# CPLD.net
KiCad netlist of a schematic drawn in Altium Designer
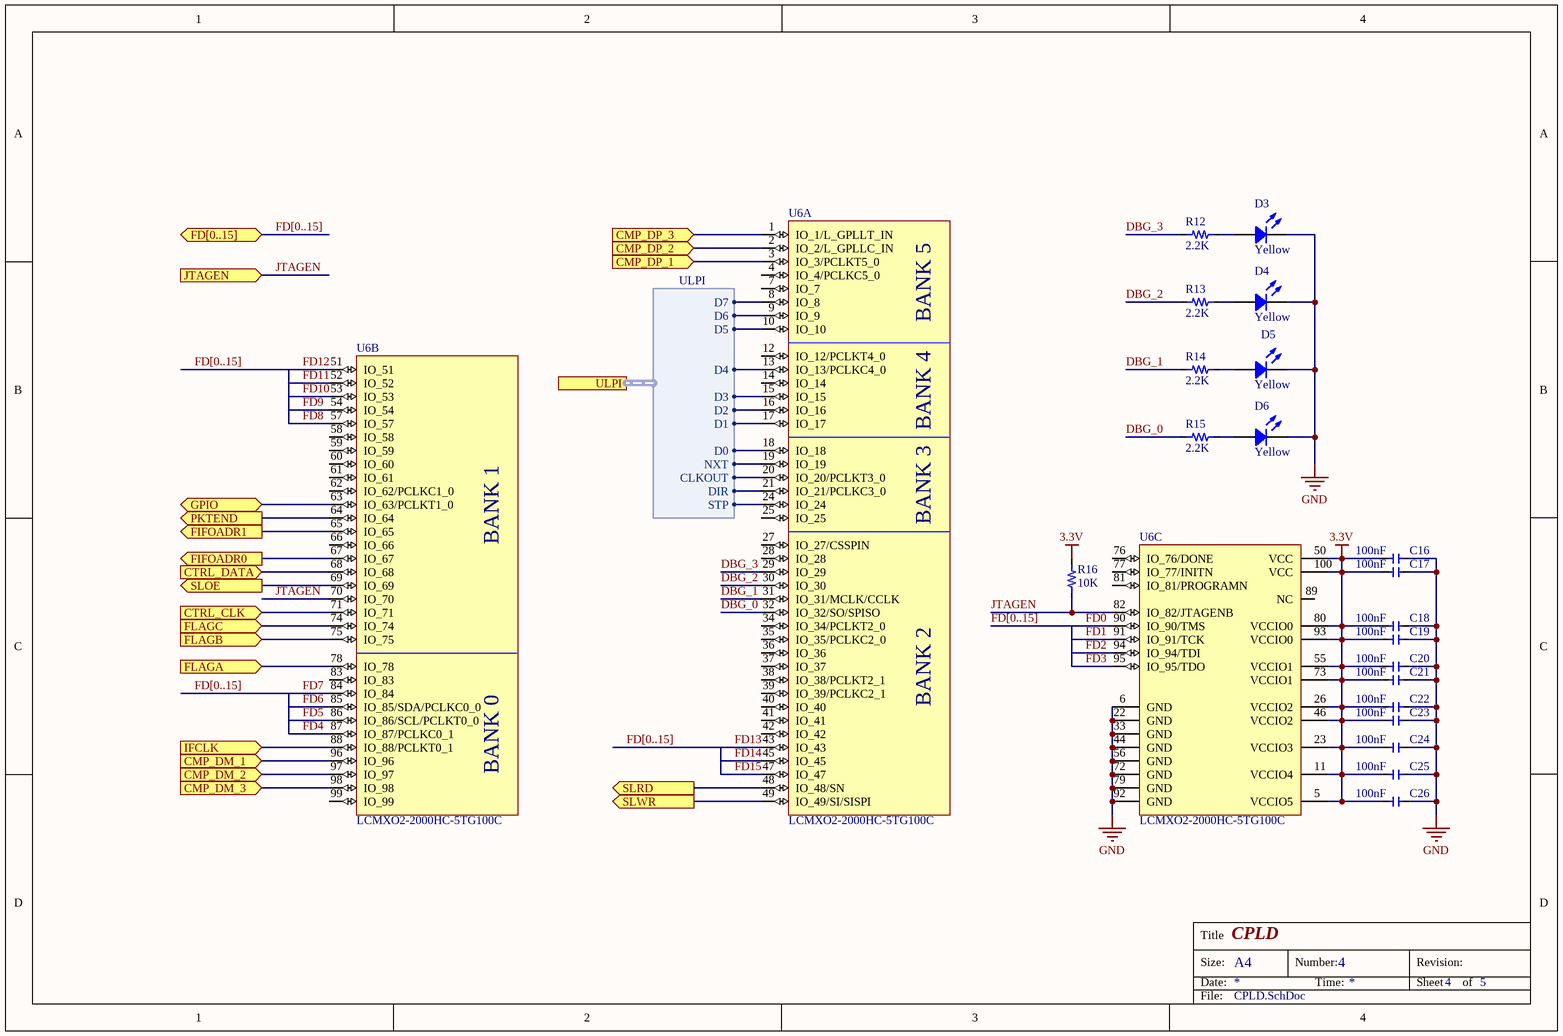
[diagram p0: CPLD.SchDoc]

(export (version "E")
  (design (tool "Eeschema 10.0.6"))
  (components
    (comp (ref "C16")
      (value "100nF")
      (footprint "CAP 0402/1005")
      (description "CAP CER 100NF 25V X5R 0402")
      (fields (field (name "PART NUMBER") "GRM155R61E104KA87D") (field (name "MANUFACTURER") "Murata"))
      (libsource (lib "Mengsklib") (part "Capacitor"))
    )
    (comp (ref "C17")
      (value "100nF")
      (footprint "CAP 0402/1005")
      (description "CAP CER 100NF 25V X5R 0402")
      (fields (field (name "PART NUMBER") "GRM155R61E104KA87D") (field (name "MANUFACTURER") "Murata"))
      (libsource (lib "Mengsklib") (part "Capacitor"))
    )
    (comp (ref "C18")
      (value "100nF")
      (footprint "CAP 0402/1005")
      (description "CAP CER 100NF 25V X5R 0402")
      (fields (field (name "PART NUMBER") "GRM155R61E104KA87D") (field (name "MANUFACTURER") "Murata"))
      (libsource (lib "Mengsklib") (part "Capacitor"))
    )
    (comp (ref "C19")
      (value "100nF")
      (footprint "CAP 0402/1005")
      (description "CAP CER 100NF 25V X5R 0402")
      (fields (field (name "PART NUMBER") "GRM155R61E104KA87D") (field (name "MANUFACTURER") "Murata"))
      (libsource (lib "Mengsklib") (part "Capacitor"))
    )
    (comp (ref "C20")
      (value "100nF")
      (footprint "CAP 0402/1005")
      (description "CAP CER 100NF 25V X5R 0402")
      (fields (field (name "PART NUMBER") "GRM155R61E104KA87D") (field (name "MANUFACTURER") "Murata"))
      (libsource (lib "Mengsklib") (part "Capacitor"))
    )
    (comp (ref "C21")
      (value "100nF")
      (footprint "CAP 0402/1005")
      (description "CAP CER 100NF 25V X5R 0402")
      (fields (field (name "PART NUMBER") "GRM155R61E104KA87D") (field (name "MANUFACTURER") "Murata"))
      (libsource (lib "Mengsklib") (part "Capacitor"))
    )
    (comp (ref "C22")
      (value "100nF")
      (footprint "CAP 0402/1005")
      (description "CAP CER 100NF 25V X5R 0402")
      (fields (field (name "PART NUMBER") "GRM155R61E104KA87D") (field (name "MANUFACTURER") "Murata"))
      (libsource (lib "Mengsklib") (part "Capacitor"))
    )
    (comp (ref "C23")
      (value "100nF")
      (footprint "CAP 0402/1005")
      (description "CAP CER 100NF 25V X5R 0402")
      (fields (field (name "PART NUMBER") "GRM155R61E104KA87D") (field (name "MANUFACTURER") "Murata"))
      (libsource (lib "Mengsklib") (part "Capacitor"))
    )
    (comp (ref "C24")
      (value "100nF")
      (footprint "CAP 0402/1005")
      (description "CAP CER 100NF 25V X5R 0402")
      (fields (field (name "PART NUMBER") "GRM155R61E104KA87D") (field (name "MANUFACTURER") "Murata"))
      (libsource (lib "Mengsklib") (part "Capacitor"))
    )
    (comp (ref "C25")
      (value "100nF")
      (footprint "CAP 0402/1005")
      (description "CAP CER 100NF 25V X5R 0402")
      (fields (field (name "PART NUMBER") "GRM155R61E104KA87D") (field (name "MANUFACTURER") "Murata"))
      (libsource (lib "Mengsklib") (part "Capacitor"))
    )
    (comp (ref "C26")
      (value "100nF")
      (footprint "CAP 0402/1005")
      (description "CAP CER 100NF 25V X5R 0402")
      (fields (field (name "PART NUMBER") "GRM155R61E104KA87D") (field (name "MANUFACTURER") "Murata"))
      (libsource (lib "Mengsklib") (part "Capacitor"))
    )
    (comp (ref "D3")
      (value "Yellow")
      (footprint "LED 0603/1608 YELLOW")
      (description "LED YELLOW CLEAR 0603 SMD")
      (fields
        (field (name "COLOUR") "Yellow")
        (field (name "PART NUMBER") "LTST-C191KSKT")
        (field (name "MANUFACTURER") "Lite-On Inc.")
      )
      (libsource (lib "Mengsklib") (part "LED"))
    )
    (comp (ref "D4")
      (value "Yellow")
      (footprint "LED 0603/1608 YELLOW")
      (description "LED YELLOW CLEAR 0603 SMD")
      (fields
        (field (name "COLOUR") "Yellow")
        (field (name "PART NUMBER") "LTST-C191KSKT")
        (field (name "MANUFACTURER") "Lite-On Inc.")
      )
      (libsource (lib "Mengsklib") (part "LED"))
    )
    (comp (ref "D5")
      (value "Yellow")
      (footprint "LED 0603/1608 YELLOW")
      (description "LED YELLOW CLEAR 0603 SMD")
      (fields
        (field (name "COLOUR") "Yellow")
        (field (name "PART NUMBER") "LTST-C191KSKT")
        (field (name "MANUFACTURER") "Lite-On Inc.")
      )
      (libsource (lib "Mengsklib") (part "LED"))
    )
    (comp (ref "D6")
      (value "Yellow")
      (footprint "LED 0603/1608 YELLOW")
      (description "LED YELLOW CLEAR 0603 SMD")
      (fields
        (field (name "COLOUR") "Yellow")
        (field (name "PART NUMBER") "LTST-C191KSKT")
        (field (name "MANUFACTURER") "Lite-On Inc.")
      )
      (libsource (lib "Mengsklib") (part "LED"))
    )
    (comp (ref "R12")
      (value "2.2K")
      (footprint "RES 0402/1005")
      (description "RES SMD 2.2K OHM 1% 1/16W 0402")
      (fields (field (name "PART NUMBER") "RC0402FR-072K2L") (field (name "MANUFACTURER") "Yageo"))
      (libsource (lib "Mengsklib") (part "Resistor"))
    )
    (comp (ref "R13")
      (value "2.2K")
      (footprint "RES 0402/1005")
      (description "RES SMD 2.2K OHM 1% 1/16W 0402")
      (fields (field (name "PART NUMBER") "RC0402FR-072K2L") (field (name "MANUFACTURER") "Yageo"))
      (libsource (lib "Mengsklib") (part "Resistor"))
    )
    (comp (ref "R14")
      (value "2.2K")
      (footprint "RES 0402/1005")
      (description "RES SMD 2.2K OHM 1% 1/16W 0402")
      (fields (field (name "PART NUMBER") "RC0402FR-072K2L") (field (name "MANUFACTURER") "Yageo"))
      (libsource (lib "Mengsklib") (part "Resistor"))
    )
    (comp (ref "R15")
      (value "2.2K")
      (footprint "RES 0402/1005")
      (description "RES SMD 2.2K OHM 1% 1/16W 0402")
      (fields (field (name "PART NUMBER") "RC0402FR-072K2L") (field (name "MANUFACTURER") "Yageo"))
      (libsource (lib "Mengsklib") (part "Resistor"))
    )
    (comp (ref "R16")
      (value "10K")
      (footprint "RES 0402/1005")
      (description "RES SMD 10K OHM 1% 1/16W 0402")
      (fields (field (name "PART NUMBER") "RC0402FR-0710KL") (field (name "MANUFACTURER") "Yageo"))
      (libsource (lib "Mengsklib") (part "Resistor"))
    )
    (comp (ref "U6")
      (value "LCMXO2-2000HC-5TG100C")
      (footprint "NXP LQFP-100 14x14mm")
      (description "FPGA, MACHXO2, 2112 LUTs")
      (fields (field (name "MANUFACTURER") "Lattice"))
      (libsource (lib "Mengsklib") (part "LCMXO2-2000HC-5TG100"))
    )
  )
  (nets
    (net (code "2") (name "/CLKOUT") (class "Default")
      (node (ref "U6") (pin "20") (pinfunction "IO_20/PCLKT3_0_20") (pintype "bidirectional"))
    )
    (net (code "3") (name "/CMP_DM_1") (class "Default")
      (node (ref "U6") (pin "96") (pinfunction "IO_96_96") (pintype "bidirectional"))
    )
    (net (code "4") (name "/CMP_DM_2") (class "Default")
      (node (ref "U6") (pin "97") (pinfunction "IO_97_97") (pintype "bidirectional"))
    )
    (net (code "5") (name "/CMP_DM_3") (class "Default")
      (node (ref "U6") (pin "98") (pinfunction "IO_98_98") (pintype "bidirectional"))
    )
    (net (code "6") (name "/CMP_DP_1") (class "Default")
      (node (ref "U6") (pin "3") (pinfunction "IO_3/PCLKT5_0_3") (pintype "bidirectional"))
    )
    (net (code "7") (name "/CMP_DP_2") (class "Default")
      (node (ref "U6") (pin "2") (pinfunction "IO_2/L_GPLLC_IN_2") (pintype "bidirectional"))
    )
    (net (code "8") (name "/CMP_DP_3") (class "Default")
      (node (ref "U6") (pin "1") (pinfunction "IO_1/L_GPLLT_IN_1") (pintype "bidirectional"))
    )
    (net (code "9") (name "/CTRL_CLK") (class "Default")
      (node (ref "U6") (pin "71") (pinfunction "IO_71_71") (pintype "bidirectional"))
    )
    (net (code "10") (name "/CTRL_DATA") (class "Default")
      (node (ref "U6") (pin "68") (pinfunction "IO_68_68") (pintype "bidirectional"))
    )
    (net (code "11") (name "/D0") (class "Default")
      (node (ref "U6") (pin "18") (pinfunction "IO_18_18") (pintype "bidirectional"))
    )
    (net (code "12") (name "/D1") (class "Default")
      (node (ref "U6") (pin "17") (pinfunction "IO_17_17") (pintype "bidirectional"))
    )
    (net (code "13") (name "/D2") (class "Default")
      (node (ref "U6") (pin "16") (pinfunction "IO_16_16") (pintype "bidirectional"))
    )
    (net (code "14") (name "/D3") (class "Default")
      (node (ref "U6") (pin "15") (pinfunction "IO_15_15") (pintype "bidirectional"))
    )
    (net (code "15") (name "/D4") (class "Default")
      (node (ref "U6") (pin "13") (pinfunction "IO_13/PCLKC4_0_13") (pintype "bidirectional"))
    )
    (net (code "16") (name "/D5") (class "Default")
      (node (ref "U6") (pin "10") (pinfunction "IO_10_10") (pintype "bidirectional"))
    )
    (net (code "17") (name "/D6") (class "Default")
      (node (ref "U6") (pin "9") (pinfunction "IO_9_9") (pintype "bidirectional"))
    )
    (net (code "18") (name "/D7") (class "Default")
      (node (ref "U6") (pin "8") (pinfunction "IO_8_8") (pintype "bidirectional"))
    )
    (net (code "19") (name "/DBG_0") (class "Default")
      (node (ref "R15") (pin "2") (pinfunction "2_2") (pintype "passive"))
      (node (ref "U6") (pin "32") (pinfunction "IO_32/SO/SPISO_32") (pintype "bidirectional"))
    )
    (net (code "20") (name "/DBG_1") (class "Default")
      (node (ref "R14") (pin "2") (pinfunction "2_2") (pintype "passive"))
      (node (ref "U6") (pin "31") (pinfunction "IO_31/MCLK/CCLK_31") (pintype "bidirectional"))
    )
    (net (code "21") (name "/DBG_2") (class "Default")
      (node (ref "R13") (pin "2") (pinfunction "2_2") (pintype "passive"))
      (node (ref "U6") (pin "30") (pinfunction "IO_30_30") (pintype "bidirectional"))
    )
    (net (code "22") (name "/DBG_3") (class "Default")
      (node (ref "R12") (pin "2") (pinfunction "2_2") (pintype "passive"))
      (node (ref "U6") (pin "29") (pinfunction "IO_29_29") (pintype "bidirectional"))
    )
    (net (code "23") (name "/DIR") (class "Default")
      (node (ref "U6") (pin "21") (pinfunction "IO_21/PCLKC3_0_21") (pintype "bidirectional"))
    )
    (net (code "24") (name "/FD0") (class "Default")
      (node (ref "U6") (pin "90") (pinfunction "IO_90/TMS_90") (pintype "bidirectional"))
    )
    (net (code "25") (name "/FD1") (class "Default")
      (node (ref "U6") (pin "91") (pinfunction "IO_91/TCK_91") (pintype "bidirectional"))
    )
    (net (code "26") (name "/FD2") (class "Default")
      (node (ref "U6") (pin "94") (pinfunction "IO_94/TDI_94") (pintype "bidirectional"))
    )
    (net (code "27") (name "/FD3") (class "Default")
      (node (ref "U6") (pin "95") (pinfunction "IO_95/TDO_95") (pintype "bidirectional"))
    )
    (net (code "28") (name "/FD4") (class "Default")
      (node (ref "U6") (pin "87") (pinfunction "IO_87/PCLKC0_1_87") (pintype "bidirectional"))
    )
    (net (code "29") (name "/FD5") (class "Default")
      (node (ref "U6") (pin "86") (pinfunction "IO_86/SCL/PCLKT0_0_86") (pintype "bidirectional"))
    )
    (net (code "30") (name "/FD6") (class "Default")
      (node (ref "U6") (pin "85") (pinfunction "IO_85/SDA/PCLKC0_0_85") (pintype "bidirectional"))
    )
    (net (code "31") (name "/FD7") (class "Default")
      (node (ref "U6") (pin "84") (pinfunction "IO_84_84") (pintype "bidirectional"))
    )
    (net (code "32") (name "/FD8") (class "Default")
      (node (ref "U6") (pin "57") (pinfunction "IO_57_57") (pintype "bidirectional"))
    )
    (net (code "33") (name "/FD9") (class "Default")
      (node (ref "U6") (pin "54") (pinfunction "IO_54_54") (pintype "bidirectional"))
    )
    (net (code "34") (name "/FD10") (class "Default")
      (node (ref "U6") (pin "53") (pinfunction "IO_53_53") (pintype "bidirectional"))
    )
    (net (code "35") (name "/FD11") (class "Default")
      (node (ref "U6") (pin "52") (pinfunction "IO_52_52") (pintype "bidirectional"))
    )
    (net (code "36") (name "/FD12") (class "Default")
      (node (ref "U6") (pin "51") (pinfunction "IO_51_51") (pintype "bidirectional"))
    )
    (net (code "37") (name "/FD13") (class "Default")
      (node (ref "U6") (pin "43") (pinfunction "IO_43_43") (pintype "bidirectional"))
    )
    (net (code "38") (name "/FD14") (class "Default")
      (node (ref "U6") (pin "45") (pinfunction "IO_45_45") (pintype "bidirectional"))
    )
    (net (code "39") (name "/FD15") (class "Default")
      (node (ref "U6") (pin "47") (pinfunction "IO_47_47") (pintype "bidirectional"))
    )
    (net (code "41") (name "/FIFOADR0") (class "Default")
      (node (ref "U6") (pin "67") (pinfunction "IO_67_67") (pintype "bidirectional"))
    )
    (net (code "42") (name "/FIFOADR1") (class "Default")
      (node (ref "U6") (pin "65") (pinfunction "IO_65_65") (pintype "bidirectional"))
    )
    (net (code "43") (name "/FLAGA") (class "Default")
      (node (ref "U6") (pin "78") (pinfunction "IO_78_78") (pintype "bidirectional"))
    )
    (net (code "44") (name "/FLAGB") (class "Default")
      (node (ref "U6") (pin "75") (pinfunction "IO_75_75") (pintype "bidirectional"))
    )
    (net (code "45") (name "/FLAGC") (class "Default")
      (node (ref "U6") (pin "74") (pinfunction "IO_74_74") (pintype "bidirectional"))
    )
    (net (code "46") (name "/GPIO") (class "Default")
      (node (ref "U6") (pin "63") (pinfunction "IO_63/PCLKT1_0_63") (pintype "bidirectional"))
    )
    (net (code "47") (name "/IFCLK") (class "Default")
      (node (ref "U6") (pin "88") (pinfunction "IO_88/PCLKT0_1_88") (pintype "bidirectional"))
    )
    (net (code "48") (name "/JTAGEN") (class "Default")
      (node (ref "R16") (pin "1") (pinfunction "1_1") (pintype "passive"))
      (node (ref "U6") (pin "70") (pinfunction "IO_70_70") (pintype "bidirectional"))
      (node (ref "U6") (pin "82") (pinfunction "IO_82/JTAGENB_82") (pintype "bidirectional"))
    )
    (net (code "49") (name "/NXT") (class "Default")
      (node (ref "U6") (pin "19") (pinfunction "IO_19_19") (pintype "bidirectional"))
    )
    (net (code "50") (name "/PKTEND") (class "Default")
      (node (ref "U6") (pin "64") (pinfunction "IO_64_64") (pintype "bidirectional"))
    )
    (net (code "51") (name "/SLOE") (class "Default")
      (node (ref "U6") (pin "69") (pinfunction "IO_69_69") (pintype "bidirectional"))
    )
    (net (code "52") (name "/SLRD") (class "Default")
      (node (ref "U6") (pin "48") (pinfunction "IO_48/SN_48") (pintype "bidirectional"))
    )
    (net (code "53") (name "/SLWR") (class "Default")
      (node (ref "U6") (pin "49") (pinfunction "IO_49/SI/SISPI_49") (pintype "bidirectional"))
    )
    (net (code "54") (name "/STP") (class "Default")
      (node (ref "U6") (pin "24") (pinfunction "IO_24_24") (pintype "bidirectional"))
    )
    (net (code "56") (name "3.3V") (class "Default")
      (node (ref "C16") (pin "1") (pinfunction "1_1") (pintype "passive"))
      (node (ref "C17") (pin "2") (pinfunction "2_2") (pintype "passive"))
      (node (ref "C18") (pin "1") (pinfunction "1_1") (pintype "passive"))
      (node (ref "C19") (pin "1") (pinfunction "1_1") (pintype "passive"))
      (node (ref "C20") (pin "1") (pinfunction "1_1") (pintype "passive"))
      (node (ref "C21") (pin "1") (pinfunction "1_1") (pintype "passive"))
      (node (ref "C22") (pin "1") (pinfunction "1_1") (pintype "passive"))
      (node (ref "C23") (pin "1") (pinfunction "1_1") (pintype "passive"))
      (node (ref "C24") (pin "1") (pinfunction "1_1") (pintype "passive"))
      (node (ref "C25") (pin "1") (pinfunction "1_1") (pintype "passive"))
      (node (ref "C26") (pin "1") (pinfunction "1_1") (pintype "passive"))
      (node (ref "R16") (pin "2") (pinfunction "2_2") (pintype "passive"))
      (node (ref "U6") (pin "100") (pinfunction "VCC_100") (pintype "passive"))
      (node (ref "U6") (pin "11") (pinfunction "VCCIO4_11") (pintype "passive"))
      (node (ref "U6") (pin "23") (pinfunction "VCCIO3_23") (pintype "passive"))
      (node (ref "U6") (pin "26") (pinfunction "VCCIO2_26") (pintype "passive"))
      (node (ref "U6") (pin "46") (pinfunction "VCCIO2_46") (pintype "passive"))
      (node (ref "U6") (pin "5") (pinfunction "VCCIO5_5") (pintype "passive"))
      (node (ref "U6") (pin "50") (pinfunction "VCC_50") (pintype "passive"))
      (node (ref "U6") (pin "55") (pinfunction "VCCIO1_55") (pintype "passive"))
      (node (ref "U6") (pin "73") (pinfunction "VCCIO1_73") (pintype "passive"))
      (node (ref "U6") (pin "80") (pinfunction "VCCIO0_80") (pintype "passive"))
      (node (ref "U6") (pin "93") (pinfunction "VCCIO0_93") (pintype "passive"))
    )
    (net (code "57") (name "GND") (class "Default")
      (node (ref "C16") (pin "2") (pinfunction "2_2") (pintype "passive"))
      (node (ref "C17") (pin "1") (pinfunction "1_1") (pintype "passive"))
      (node (ref "C18") (pin "2") (pinfunction "2_2") (pintype "passive"))
      (node (ref "C19") (pin "2") (pinfunction "2_2") (pintype "passive"))
      (node (ref "C20") (pin "2") (pinfunction "2_2") (pintype "passive"))
      (node (ref "C21") (pin "2") (pinfunction "2_2") (pintype "passive"))
      (node (ref "C22") (pin "2") (pinfunction "2_2") (pintype "passive"))
      (node (ref "C23") (pin "2") (pinfunction "2_2") (pintype "passive"))
      (node (ref "C24") (pin "2") (pinfunction "2_2") (pintype "passive"))
      (node (ref "C25") (pin "2") (pinfunction "2_2") (pintype "passive"))
      (node (ref "C26") (pin "2") (pinfunction "2_2") (pintype "passive"))
      (node (ref "D3") (pin "2") (pinfunction "2_2") (pintype "passive"))
      (node (ref "D4") (pin "2") (pinfunction "2_2") (pintype "passive"))
      (node (ref "D5") (pin "2") (pinfunction "2_2") (pintype "passive"))
      (node (ref "D6") (pin "2") (pinfunction "2_2") (pintype "passive"))
      (node (ref "U6") (pin "22") (pinfunction "GND_22") (pintype "passive"))
      (node (ref "U6") (pin "33") (pinfunction "GND_33") (pintype "passive"))
      (node (ref "U6") (pin "44") (pinfunction "GND_44") (pintype "passive"))
      (node (ref "U6") (pin "56") (pinfunction "GND_56") (pintype "passive"))
      (node (ref "U6") (pin "6") (pinfunction "GND_6") (pintype "passive"))
      (node (ref "U6") (pin "72") (pinfunction "GND_72") (pintype "passive"))
      (node (ref "U6") (pin "79") (pinfunction "GND_79") (pintype "passive"))
      (node (ref "U6") (pin "92") (pinfunction "GND_92") (pintype "passive"))
    )
    (net (code "58") (name "Net-(D3-Pad1)") (class "Default")
      (node (ref "D3") (pin "1") (pinfunction "1_1") (pintype "passive"))
      (node (ref "R12") (pin "1") (pinfunction "1_1") (pintype "passive"))
    )
    (net (code "59") (name "Net-(D4-Pad1)") (class "Default")
      (node (ref "D4") (pin "1") (pinfunction "1_1") (pintype "passive"))
      (node (ref "R13") (pin "1") (pinfunction "1_1") (pintype "passive"))
    )
    (net (code "60") (name "Net-(D5-Pad1)") (class "Default")
      (node (ref "D5") (pin "1") (pinfunction "1_1") (pintype "passive"))
      (node (ref "R14") (pin "1") (pinfunction "1_1") (pintype "passive"))
    )
    (net (code "61") (name "Net-(D6-Pad1)") (class "Default")
      (node (ref "D6") (pin "1") (pinfunction "1_1") (pintype "passive"))
      (node (ref "R15") (pin "1") (pinfunction "1_1") (pintype "passive"))
    )
    (net (code "62") (name "unconnected-(U6A-IO_4{slash}PCLKC5_0-Pad4)") (class "Default")
      (node (ref "U6") (pin "4") (pinfunction "IO_4/PCLKC5_0_4") (pintype "bidirectional"))
    )
    (net (code "63") (name "unconnected-(U6A-IO_7-Pad7)") (class "Default")
      (node (ref "U6") (pin "7") (pinfunction "IO_7_7") (pintype "bidirectional"))
    )
    (net (code "64") (name "unconnected-(U6A-IO_12{slash}PCLKT4_0-Pad12)") (class "Default")
      (node (ref "U6") (pin "12") (pinfunction "IO_12/PCLKT4_0_12") (pintype "bidirectional"))
    )
    (net (code "65") (name "unconnected-(U6A-IO_14-Pad14)") (class "Default")
      (node (ref "U6") (pin "14") (pinfunction "IO_14_14") (pintype "bidirectional"))
    )
    (net (code "66") (name "unconnected-(U6A-IO_25-Pad25)") (class "Default")
      (node (ref "U6") (pin "25") (pinfunction "IO_25_25") (pintype "bidirectional"))
    )
    (net (code "67") (name "unconnected-(U6A-IO_27{slash}CSSPIN-Pad27)") (class "Default")
      (node (ref "U6") (pin "27") (pinfunction "IO_27/CSSPIN_27") (pintype "bidirectional"))
    )
    (net (code "68") (name "unconnected-(U6A-IO_28-Pad28)") (class "Default")
      (node (ref "U6") (pin "28") (pinfunction "IO_28_28") (pintype "bidirectional"))
    )
    (net (code "69") (name "unconnected-(U6A-IO_34{slash}PCLKT2_0-Pad34)") (class "Default")
      (node (ref "U6") (pin "34") (pinfunction "IO_34/PCLKT2_0_34") (pintype "bidirectional"))
    )
    (net (code "70") (name "unconnected-(U6A-IO_35{slash}PCLKC2_0-Pad35)") (class "Default")
      (node (ref "U6") (pin "35") (pinfunction "IO_35/PCLKC2_0_35") (pintype "bidirectional"))
    )
    (net (code "71") (name "unconnected-(U6A-IO_36-Pad36)") (class "Default")
      (node (ref "U6") (pin "36") (pinfunction "IO_36_36") (pintype "bidirectional"))
    )
    (net (code "72") (name "unconnected-(U6A-IO_37-Pad37)") (class "Default")
      (node (ref "U6") (pin "37") (pinfunction "IO_37_37") (pintype "bidirectional"))
    )
    (net (code "73") (name "unconnected-(U6A-IO_38{slash}PCLKT2_1-Pad38)") (class "Default")
      (node (ref "U6") (pin "38") (pinfunction "IO_38/PCLKT2_1_38") (pintype "bidirectional"))
    )
    (net (code "74") (name "unconnected-(U6A-IO_39{slash}PCLKC2_1-Pad39)") (class "Default")
      (node (ref "U6") (pin "39") (pinfunction "IO_39/PCLKC2_1_39") (pintype "bidirectional"))
    )
    (net (code "75") (name "unconnected-(U6A-IO_40-Pad40)") (class "Default")
      (node (ref "U6") (pin "40") (pinfunction "IO_40_40") (pintype "bidirectional"))
    )
    (net (code "76") (name "unconnected-(U6A-IO_41-Pad41)") (class "Default")
      (node (ref "U6") (pin "41") (pinfunction "IO_41_41") (pintype "bidirectional"))
    )
    (net (code "77") (name "unconnected-(U6A-IO_42-Pad42)") (class "Default")
      (node (ref "U6") (pin "42") (pinfunction "IO_42_42") (pintype "bidirectional"))
    )
    (net (code "78") (name "unconnected-(U6B-IO_58-Pad58)") (class "Default")
      (node (ref "U6") (pin "58") (pinfunction "IO_58_58") (pintype "bidirectional"))
    )
    (net (code "79") (name "unconnected-(U6B-IO_59-Pad59)") (class "Default")
      (node (ref "U6") (pin "59") (pinfunction "IO_59_59") (pintype "bidirectional"))
    )
    (net (code "80") (name "unconnected-(U6B-IO_60-Pad60)") (class "Default")
      (node (ref "U6") (pin "60") (pinfunction "IO_60_60") (pintype "bidirectional"))
    )
    (net (code "81") (name "unconnected-(U6B-IO_61-Pad61)") (class "Default")
      (node (ref "U6") (pin "61") (pinfunction "IO_61_61") (pintype "bidirectional"))
    )
    (net (code "82") (name "unconnected-(U6B-IO_62{slash}PCLKC1_0-Pad62)") (class "Default")
      (node (ref "U6") (pin "62") (pinfunction "IO_62/PCLKC1_0_62") (pintype "bidirectional"))
    )
    (net (code "83") (name "unconnected-(U6B-IO_66-Pad66)") (class "Default")
      (node (ref "U6") (pin "66") (pinfunction "IO_66_66") (pintype "bidirectional"))
    )
    (net (code "84") (name "unconnected-(U6B-IO_83-Pad83)") (class "Default")
      (node (ref "U6") (pin "83") (pinfunction "IO_83_83") (pintype "bidirectional"))
    )
    (net (code "85") (name "unconnected-(U6B-IO_99-Pad99)") (class "Default")
      (node (ref "U6") (pin "99") (pinfunction "IO_99_99") (pintype "bidirectional"))
    )
    (net (code "86") (name "unconnected-(U6C-IO_76{slash}DONE-Pad76)") (class "Default")
      (node (ref "U6") (pin "76") (pinfunction "IO_76/DONE_76") (pintype "bidirectional"))
    )
    (net (code "87") (name "unconnected-(U6C-IO_77{slash}INITN-Pad77)") (class "Default")
      (node (ref "U6") (pin "77") (pinfunction "IO_77/INITN_77") (pintype "bidirectional"))
    )
    (net (code "88") (name "unconnected-(U6C-IO_81{slash}PROGRAMN-Pad81)") (class "Default")
      (node (ref "U6") (pin "81") (pinfunction "IO_81/PROGRAMN_81") (pintype "bidirectional"))
    )
    (net (code "89") (name "unconnected-(U6C-NC-Pad89)") (class "Default")
      (node (ref "U6") (pin "89") (pinfunction "NC_89") (pintype "passive"))
    )
  )
)
